# Regulation_PID.net
KiCad netlist of a schematic drawn in Altium Designer
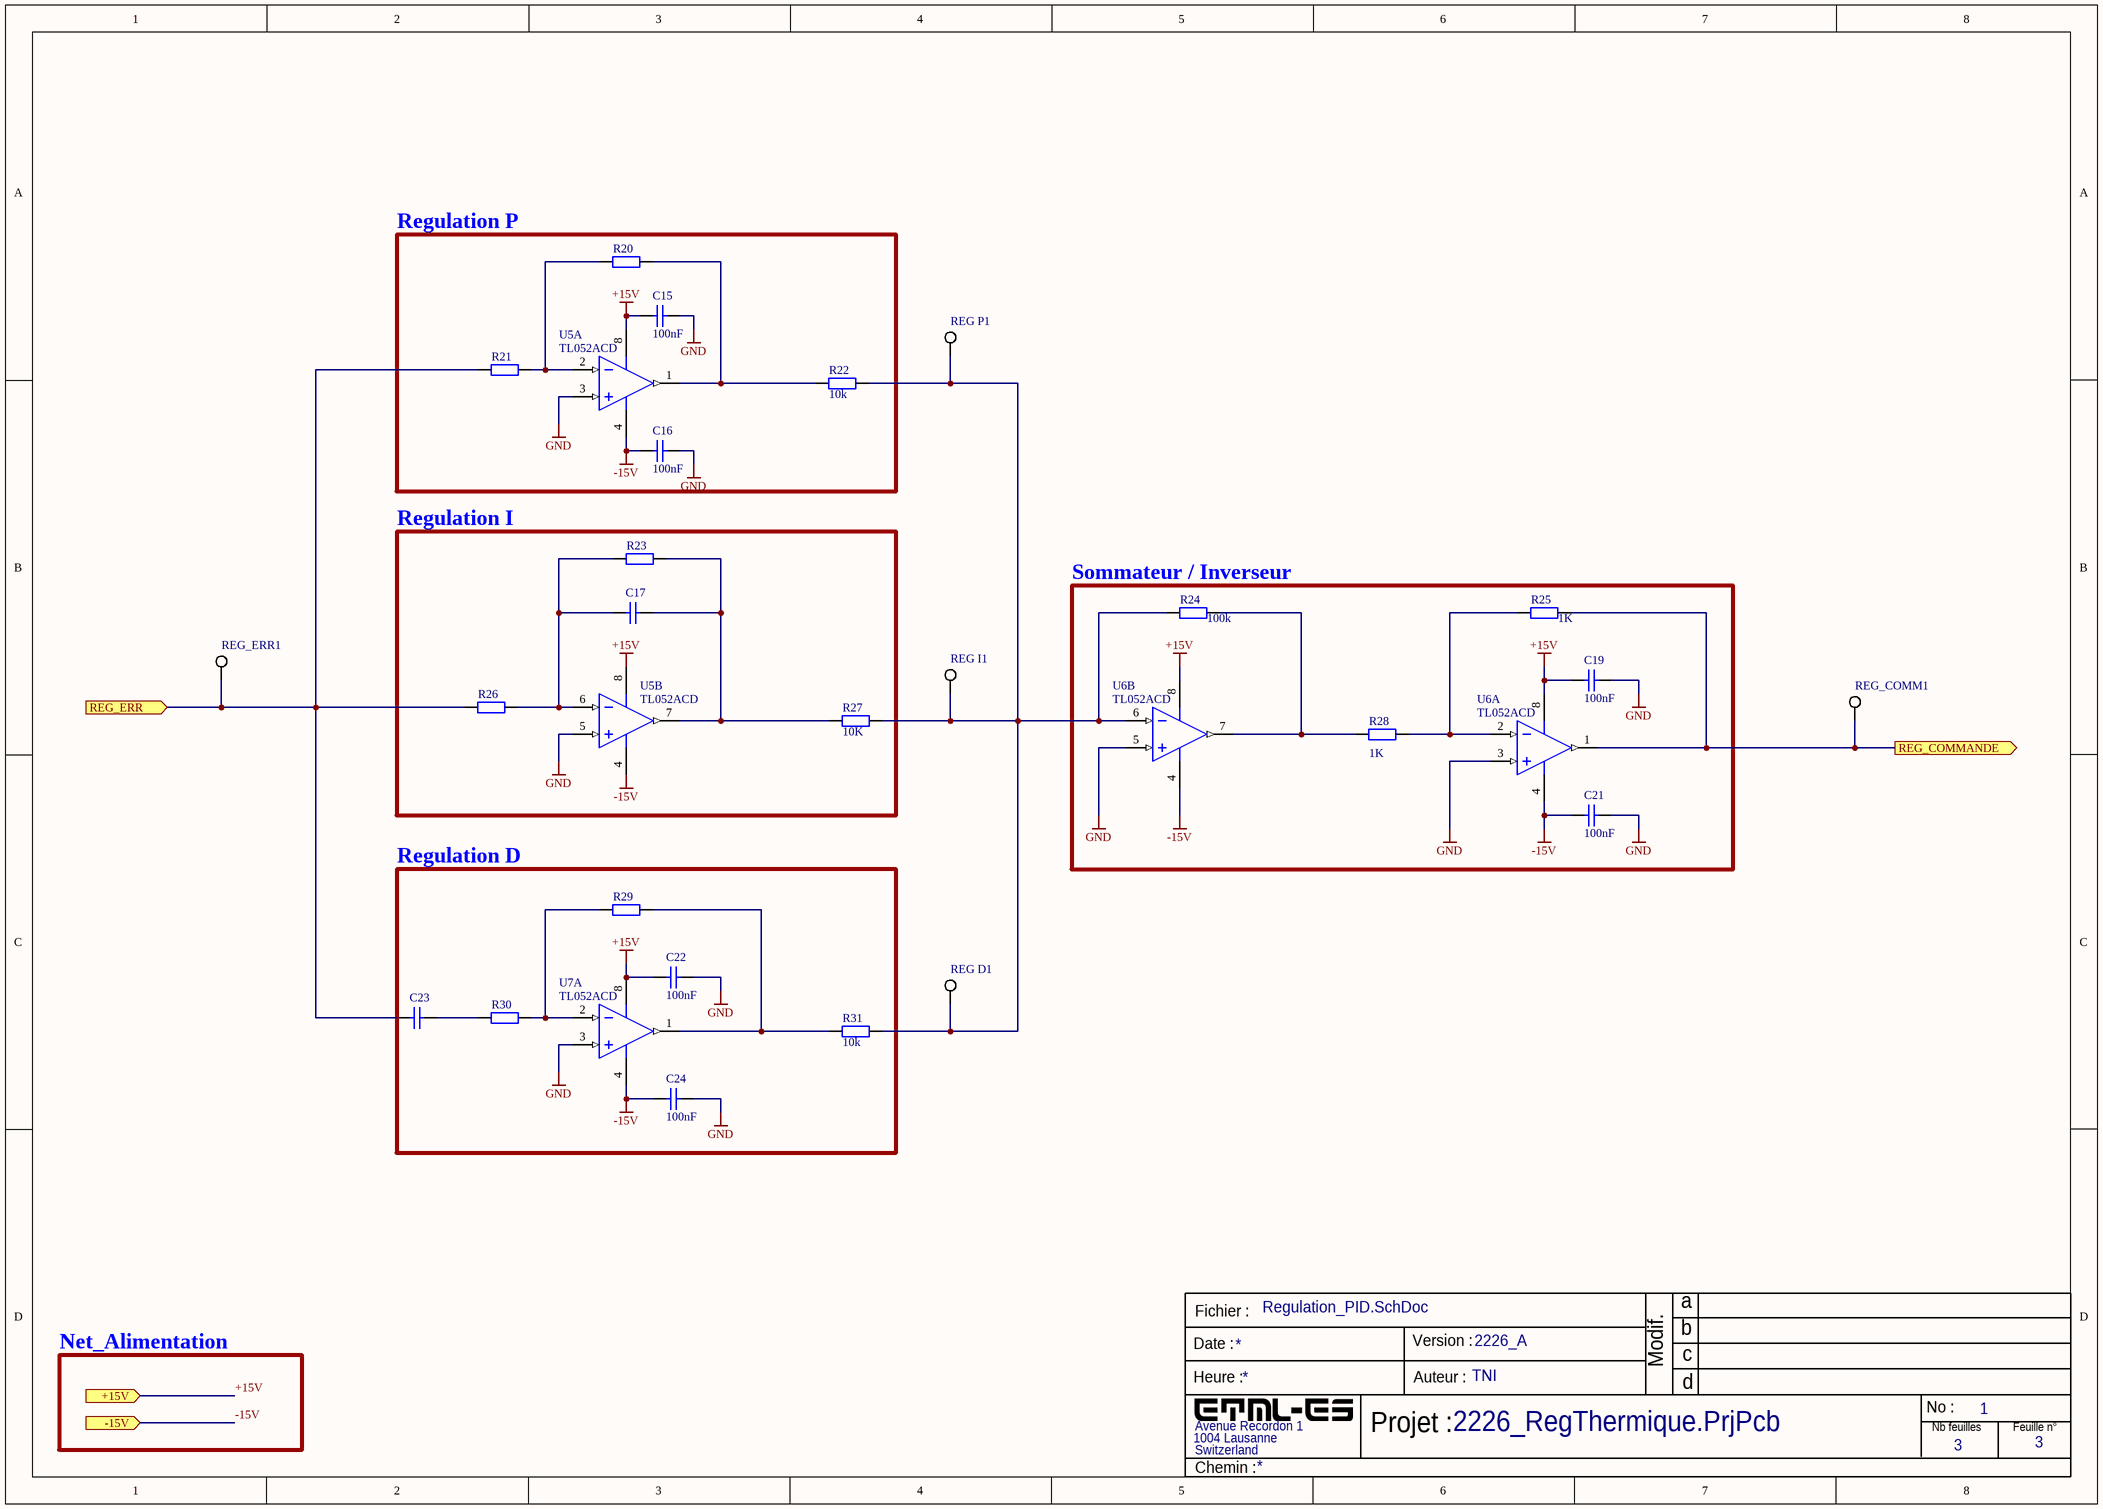
[diagram p0: Regulation_PID.SchDoc]

(export (version "E")
  (design (tool "Eeschema 10.0.6"))
  (components
    (comp (ref "C15")
      (value "100nF")
      (footprint "C0805")
      (description "Cap 100nF")
      (fields (field (name "Comment") "Cap") (field (name "PUBLISHER") "Altium Limited"))
      (libsource (lib "Miscellaneous Devices") (part "Cap"))
    )
    (comp (ref "C16")
      (value "100nF")
      (footprint "C0805")
      (description "Cap 100nF")
      (fields (field (name "Comment") "Cap") (field (name "PUBLISHER") "Altium Limited"))
      (libsource (lib "Miscellaneous Devices") (part "Cap"))
    )
    (comp (ref "C17")
      (value "Cap")
      (footprint "AXIAL-0.4")
      (description "Capacitor")
      (fields (field (name "PUBLISHER") "Altium Limited"))
      (libsource (lib "Miscellaneous Devices") (part "Cap"))
    )
    (comp (ref "C19")
      (value "100nF")
      (footprint "C0805")
      (description "Cap 100nF")
      (fields (field (name "Comment") "Cap") (field (name "PUBLISHER") "Altium Limited"))
      (libsource (lib "Miscellaneous Devices") (part "Cap"))
    )
    (comp (ref "C21")
      (value "100nF")
      (footprint "C0805")
      (description "Cap 100nF")
      (fields (field (name "Comment") "Cap") (field (name "PUBLISHER") "Altium Limited"))
      (libsource (lib "Miscellaneous Devices") (part "Cap"))
    )
    (comp (ref "C22")
      (value "100nF")
      (footprint "C0805")
      (description "Cap 100nF")
      (fields (field (name "Comment") "Cap") (field (name "PUBLISHER") "Altium Limited"))
      (libsource (lib "Miscellaneous Devices") (part "Cap"))
    )
    (comp (ref "C23")
      (value "Cap")
      (footprint "AXIAL-0.4")
      (description "Capacitor")
      (fields (field (name "PUBLISHER") "Altium Limited"))
      (libsource (lib "Miscellaneous Devices") (part "Cap"))
    )
    (comp (ref "C24")
      (value "100nF")
      (footprint "C0805")
      (description "Cap 100nF")
      (fields (field (name "Comment") "Cap") (field (name "PUBLISHER") "Altium Limited"))
      (libsource (lib "Miscellaneous Devices") (part "Cap"))
    )
    (comp (ref "R20")
      (value "Res2")
      (footprint "AXIAL-0.4")
      (description "Resistor")
      (fields (field (name "PUBLISHER") "Altium Limited"))
      (libsource (lib "Miscellaneous Devices") (part "Res2"))
    )
    (comp (ref "R21")
      (value "Res2")
      (footprint "AXIAL-0.4")
      (description "Resistor")
      (fields (field (name "PUBLISHER") "Altium Limited"))
      (libsource (lib "Miscellaneous Devices") (part "Res2"))
    )
    (comp (ref "R22")
      (value "10k")
      (footprint "AXIAL-0.4")
      (description "Res 100k")
      (fields (field (name "PUBLISHER") "Altium Limited"))
      (libsource (lib "Miscellaneous Devices") (part "Res2"))
    )
    (comp (ref "R23")
      (value "Res2")
      (footprint "AXIAL-0.4")
      (description "Resistor")
      (fields (field (name "PUBLISHER") "Altium Limited"))
      (libsource (lib "Miscellaneous Devices") (part "Res2"))
    )
    (comp (ref "R24")
      (value "100k")
      (footprint "6-0805_N")
      (description "Res 100k")
      (fields (field (name "Comment") "Res2") (field (name "PUBLISHER") "Altium Limited"))
      (libsource (lib "Miscellaneous Devices") (part "Res2"))
    )
    (comp (ref "R25")
      (value "1K")
      (footprint "6-0805_N")
      (description "Res 1k")
      (fields (field (name "Comment") "Res2") (field (name "PUBLISHER") "Altium Limited"))
      (libsource (lib "Miscellaneous Devices") (part "Res2"))
    )
    (comp (ref "R26")
      (value "Res2")
      (footprint "AXIAL-0.4")
      (description "Resistor")
      (fields (field (name "PUBLISHER") "Altium Limited"))
      (libsource (lib "Miscellaneous Devices") (part "Res2"))
    )
    (comp (ref "R27")
      (value "10K")
      (footprint "AXIAL-0.4")
      (description "Res 100k")
      (fields (field (name "PUBLISHER") "Altium Limited"))
      (libsource (lib "Miscellaneous Devices") (part "Res2"))
    )
    (comp (ref "R28")
      (value "1K")
      (footprint "6-0805_N")
      (description "Res 1k")
      (fields (field (name "Comment") "Res2") (field (name "PUBLISHER") "Altium Limited"))
      (libsource (lib "Miscellaneous Devices") (part "Res2"))
    )
    (comp (ref "R29")
      (value "Res2")
      (footprint "AXIAL-0.4")
      (description "Resistor")
      (fields (field (name "PUBLISHER") "Altium Limited"))
      (libsource (lib "Miscellaneous Devices") (part "Res2"))
    )
    (comp (ref "R30")
      (value "Res2")
      (footprint "AXIAL-0.4")
      (description "Resistor")
      (fields (field (name "PUBLISHER") "Altium Limited"))
      (libsource (lib "Miscellaneous Devices") (part "Res2"))
    )
    (comp (ref "R31")
      (value "10k")
      (footprint "AXIAL-0.4")
      (description "Res 100k")
      (fields (field (name "PUBLISHER") "Altium Limited"))
      (libsource (lib "Miscellaneous Devices") (part "Res2"))
    )
    (comp (ref "REG D1")
      (value "REGP")
      (footprint "KSTN-5019_V")
      (description "Test Point, 1 Position SMD, RoHS, Tape and Reel")
      (libsource (lib "Altium Content Vault") (part "TESTPOINT_WHITE"))
    )
    (comp (ref "REG I1")
      (value "REGP")
      (footprint "KSTN-5019_V")
      (description "Test Point, 1 Position SMD, RoHS, Tape and Reel")
      (libsource (lib "Altium Content Vault") (part "TESTPOINT_WHITE"))
    )
    (comp (ref "REG P1")
      (value "REGP")
      (footprint "KSTN-5019_V")
      (description "Test Point, 1 Position SMD, RoHS, Tape and Reel")
      (libsource (lib "Altium Content Vault") (part "TESTPOINT_WHITE"))
    )
    (comp (ref "REG_COMM1")
      (value "REGP")
      (footprint "KSTN-5019_V")
      (description "Test Point, 1 Position SMD, RoHS, Tape and Reel")
      (libsource (lib "Altium Content Vault") (part "TESTPOINT_WHITE"))
    )
    (comp (ref "REG_ERR1")
      (value "REGP")
      (footprint "KSTN-5019_V")
      (description "Test Point, 1 Position SMD, RoHS, Tape and Reel")
      (libsource (lib "Altium Content Vault") (part "TESTPOINT_WHITE"))
    )
    (comp (ref "U5")
      (value "TL052ACD")
      (footprint "D0008A_N")
      (fields (field (name "MANUFACTURER") "Texas Instruments"))
      (libsource (lib "Altium Content Vault") (part "TI-AMP-D6-2-8_D"))
    )
    (comp (ref "U6")
      (value "TL052ACD")
      (footprint "D0008A_N")
      (fields (field (name "MANUFACTURER") "Texas Instruments"))
      (libsource (lib "Altium Content Vault") (part "TI-AMP-D6-2-8_D"))
    )
    (comp (ref "U7")
      (value "TL052ACD")
      (footprint "D0008A_N")
      (fields (field (name "MANUFACTURER") "Texas Instruments"))
      (libsource (lib "Altium Content Vault") (part "TI-AMP-D6-2-8_D"))
    )
  )
  (nets
    (net (code "1") (name "+15V") (class "Default")
      (node (ref "C15") (pin "2") (pinfunction "2_2") (pintype "passive"))
      (node (ref "C19") (pin "2") (pinfunction "2_2") (pintype "passive"))
      (node (ref "C22") (pin "2") (pinfunction "2_2") (pintype "passive"))
      (node (ref "U5") (pin "8") (pinfunction "VCC+_8") (pintype "passive"))
      (node (ref "U6") (pin "8") (pinfunction "VCC+_8") (pintype "passive"))
      (node (ref "U7") (pin "8") (pinfunction "VCC+_8") (pintype "passive"))
    )
    (net (code "2") (name "-15V") (class "Default")
      (node (ref "C16") (pin "2") (pinfunction "2_2") (pintype "passive"))
      (node (ref "C21") (pin "2") (pinfunction "2_2") (pintype "passive"))
      (node (ref "C24") (pin "2") (pinfunction "2_2") (pintype "passive"))
      (node (ref "U5") (pin "4") (pinfunction "VCC-_4") (pintype "passive"))
      (node (ref "U6") (pin "4") (pinfunction "VCC-_4") (pintype "passive"))
      (node (ref "U7") (pin "4") (pinfunction "VCC-_4") (pintype "passive"))
    )
    (net (code "3") (name "/REG_COMMANDE") (class "Default")
      (node (ref "R25") (pin "2") (pinfunction "2_2") (pintype "passive"))
      (node (ref "REG_COMM1") (pin "1") (pinfunction "1_1") (pintype "passive"))
      (node (ref "U6") (pin "1") (pinfunction "OUT1_1") (pintype "output"))
    )
    (net (code "4") (name "/REG_ERR") (class "Default")
      (node (ref "C23") (pin "2") (pinfunction "2_2") (pintype "passive"))
      (node (ref "R21") (pin "1") (pinfunction "1_1") (pintype "passive"))
      (node (ref "R26") (pin "1") (pinfunction "1_1") (pintype "passive"))
      (node (ref "REG_ERR1") (pin "1") (pinfunction "1_1") (pintype "passive"))
    )
    (net (code "5") (name "GND") (class "Default")
      (node (ref "C15") (pin "1") (pinfunction "1_1") (pintype "passive"))
      (node (ref "C16") (pin "1") (pinfunction "1_1") (pintype "passive"))
      (node (ref "C19") (pin "1") (pinfunction "1_1") (pintype "passive"))
      (node (ref "C21") (pin "1") (pinfunction "1_1") (pintype "passive"))
      (node (ref "C22") (pin "1") (pinfunction "1_1") (pintype "passive"))
      (node (ref "C24") (pin "1") (pinfunction "1_1") (pintype "passive"))
      (node (ref "U5") (pin "3") (pinfunction "IN1+_3") (pintype "input"))
      (node (ref "U5") (pin "5") (pinfunction "IN2+_5") (pintype "input"))
      (node (ref "U6") (pin "3") (pinfunction "IN1+_3") (pintype "input"))
      (node (ref "U6") (pin "5") (pinfunction "IN2+_5") (pintype "input"))
      (node (ref "U7") (pin "3") (pinfunction "IN1+_3") (pintype "input"))
    )
    (net (code "6") (name "Net-(C23-Pad1)") (class "Default")
      (node (ref "C23") (pin "1") (pinfunction "1_1") (pintype "passive"))
      (node (ref "R30") (pin "1") (pinfunction "1_1") (pintype "passive"))
    )
    (net (code "7") (name "Net-(U5A-IN1-)") (class "Default")
      (node (ref "R20") (pin "1") (pinfunction "1_1") (pintype "passive"))
      (node (ref "R21") (pin "2") (pinfunction "2_2") (pintype "passive"))
      (node (ref "U5") (pin "2") (pinfunction "IN1-_2") (pintype "input"))
    )
    (net (code "8") (name "Net-(U5A-OUT1)") (class "Default")
      (node (ref "R20") (pin "2") (pinfunction "2_2") (pintype "passive"))
      (node (ref "R22") (pin "1") (pinfunction "1_1") (pintype "passive"))
      (node (ref "U5") (pin "1") (pinfunction "OUT1_1") (pintype "output"))
    )
    (net (code "9") (name "Net-(U5B-IN2-)") (class "Default")
      (node (ref "C17") (pin "2") (pinfunction "2_2") (pintype "passive"))
      (node (ref "R23") (pin "1") (pinfunction "1_1") (pintype "passive"))
      (node (ref "R26") (pin "2") (pinfunction "2_2") (pintype "passive"))
      (node (ref "U5") (pin "6") (pinfunction "IN2-_6") (pintype "input"))
    )
    (net (code "10") (name "Net-(U5B-OUT2)") (class "Default")
      (node (ref "C17") (pin "1") (pinfunction "1_1") (pintype "passive"))
      (node (ref "R23") (pin "2") (pinfunction "2_2") (pintype "passive"))
      (node (ref "R27") (pin "1") (pinfunction "1_1") (pintype "passive"))
      (node (ref "U5") (pin "7") (pinfunction "OUT2_7") (pintype "output"))
    )
    (net (code "11") (name "Net-(U6A-IN1-)") (class "Default")
      (node (ref "R25") (pin "1") (pinfunction "1_1") (pintype "passive"))
      (node (ref "R28") (pin "2") (pinfunction "2_2") (pintype "passive"))
      (node (ref "U6") (pin "2") (pinfunction "IN1-_2") (pintype "input"))
    )
    (net (code "12") (name "Net-(U6B-IN2-)") (class "Default")
      (node (ref "R22") (pin "2") (pinfunction "2_2") (pintype "passive"))
      (node (ref "R24") (pin "1") (pinfunction "1_1") (pintype "passive"))
      (node (ref "R27") (pin "2") (pinfunction "2_2") (pintype "passive"))
      (node (ref "R31") (pin "2") (pinfunction "2_2") (pintype "passive"))
      (node (ref "REG D1") (pin "1") (pinfunction "1_1") (pintype "passive"))
      (node (ref "REG I1") (pin "1") (pinfunction "1_1") (pintype "passive"))
      (node (ref "REG P1") (pin "1") (pinfunction "1_1") (pintype "passive"))
      (node (ref "U6") (pin "6") (pinfunction "IN2-_6") (pintype "input"))
    )
    (net (code "13") (name "Net-(U6B-OUT2)") (class "Default")
      (node (ref "R24") (pin "2") (pinfunction "2_2") (pintype "passive"))
      (node (ref "R28") (pin "1") (pinfunction "1_1") (pintype "passive"))
      (node (ref "U6") (pin "7") (pinfunction "OUT2_7") (pintype "output"))
    )
    (net (code "14") (name "Net-(U7A-IN1-)") (class "Default")
      (node (ref "R29") (pin "1") (pinfunction "1_1") (pintype "passive"))
      (node (ref "R30") (pin "2") (pinfunction "2_2") (pintype "passive"))
      (node (ref "U7") (pin "2") (pinfunction "IN1-_2") (pintype "input"))
    )
    (net (code "15") (name "Net-(U7A-OUT1)") (class "Default")
      (node (ref "R29") (pin "2") (pinfunction "2_2") (pintype "passive"))
      (node (ref "R31") (pin "1") (pinfunction "1_1") (pintype "passive"))
      (node (ref "U7") (pin "1") (pinfunction "OUT1_1") (pintype "output"))
    )
  )
)
